# button_board_v0_3_1.net
KiCad netlist of a schematic drawn in EAGLE
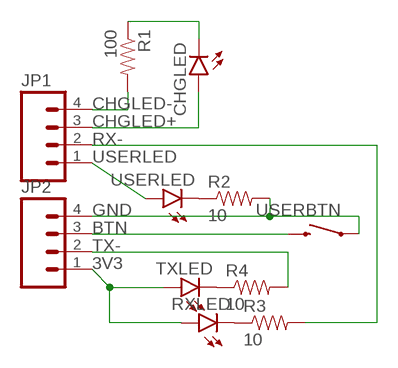
[diagram p0: schematic, sheet 1]

(export (version "E")
  (design (tool "Eeschema 10.0.6"))
  (components
    (comp (ref "CHGLED")
      (value "LED-FKIT-1206")
      (footprint "eagle-import:FKIT-LED-1206")
      (libsource (lib "eagle-import") (part "LED-FKIT-1206"))
    )
    (comp (ref "JP1")
      (value "M04PTH")
      (footprint "eagle-import:1X04")
      (libsource (lib "eagle-import") (part "M04PTH"))
    )
    (comp (ref "JP2")
      (value "M04PTH")
      (footprint "eagle-import:1X04")
      (libsource (lib "eagle-import") (part "M04PTH"))
    )
    (comp (ref "R1")
      (value "100")
      (footprint "eagle-import:0603-RES")
      (libsource (lib "eagle-import") (part "RESISTOR0603-RES"))
    )
    (comp (ref "R2")
      (value "10")
      (footprint "eagle-import:0603-RES")
      (libsource (lib "eagle-import") (part "RESISTOR0603-RES"))
    )
    (comp (ref "R3")
      (value "10")
      (footprint "eagle-import:0603-RES")
      (libsource (lib "eagle-import") (part "RESISTOR0603-RES"))
    )
    (comp (ref "R4")
      (value "10")
      (footprint "eagle-import:0603-RES")
      (libsource (lib "eagle-import") (part "RESISTOR0603-RES"))
    )
    (comp (ref "RXLED")
      (value "LED-FKIT-1206")
      (footprint "eagle-import:FKIT-LED-1206")
      (libsource (lib "eagle-import") (part "LED-FKIT-1206"))
    )
    (comp (ref "TXLED")
      (value "LED-FKIT-1206")
      (footprint "eagle-import:FKIT-LED-1206")
      (libsource (lib "eagle-import") (part "LED-FKIT-1206"))
    )
    (comp (ref "USERBTN")
      (value "SWITCH-MOMENTARY-2PCB_MOUNTSMD_OMRON_B3S_100X")
      (footprint "eagle-import:TACTILE_SWITCH_LARGE")
      (libsource (lib "eagle-import") (part "SWITCH-MOMENTARY-2SMD_OMRON_B3S_100XPCB_MOUNT"))
    )
    (comp (ref "USERLED")
      (value "LED-FKIT-1206")
      (footprint "eagle-import:FKIT-LED-1206")
      (libsource (lib "eagle-import") (part "LED-FKIT-1206"))
    )
  )
  (nets
    (net (code "1") (name "/3V3") (class "Default")
      (node (ref "JP2") (pin "1") (pinfunction "1_1") (pintype "passive"))
      (node (ref "RXLED") (pin "A") (pinfunction "A_A") (pintype "passive"))
      (node (ref "TXLED") (pin "A") (pinfunction "A_A") (pintype "passive"))
    )
    (net (code "2") (name "/BTN") (class "Default")
      (node (ref "JP2") (pin "3") (pinfunction "3_3") (pintype "passive"))
      (node (ref "USERBTN") (pin "3") (pinfunction "2_3") (pintype "passive"))
    )
    (net (code "3") (name "/CHGLED+") (class "Default")
      (node (ref "CHGLED") (pin "A") (pinfunction "A_A") (pintype "passive"))
      (node (ref "JP1") (pin "3") (pinfunction "3_3") (pintype "passive"))
    )
    (net (code "4") (name "/CHGLED-") (class "Default")
      (node (ref "JP1") (pin "4") (pinfunction "4_4") (pintype "passive"))
      (node (ref "R1") (pin "2") (pinfunction "2_2") (pintype "passive"))
    )
    (net (code "5") (name "/GND") (class "Default")
      (node (ref "JP2") (pin "4") (pinfunction "4_4") (pintype "passive"))
      (node (ref "R2") (pin "2") (pinfunction "2_2") (pintype "passive"))
      (node (ref "USERBTN") (pin "1") (pinfunction "1_1") (pintype "passive"))
    )
    (net (code "6") (name "/RX-") (class "Default")
      (node (ref "JP1") (pin "2") (pinfunction "2_2") (pintype "passive"))
      (node (ref "R3") (pin "2") (pinfunction "2_2") (pintype "passive"))
    )
    (net (code "7") (name "/TX-") (class "Default")
      (node (ref "JP2") (pin "2") (pinfunction "2_2") (pintype "passive"))
      (node (ref "R4") (pin "2") (pinfunction "2_2") (pintype "passive"))
    )
    (net (code "8") (name "/USERLED") (class "Default")
      (node (ref "JP1") (pin "1") (pinfunction "1_1") (pintype "passive"))
      (node (ref "USERLED") (pin "A") (pinfunction "A_A") (pintype "passive"))
    )
    (net (code "9") (name "Net-(CHGLED-PadC)") (class "Default")
      (node (ref "CHGLED") (pin "C") (pinfunction "C_C") (pintype "passive"))
      (node (ref "R1") (pin "1") (pinfunction "1_1") (pintype "passive"))
    )
    (net (code "10") (name "Net-(R2-Pad1)") (class "Default")
      (node (ref "R2") (pin "1") (pinfunction "1_1") (pintype "passive"))
      (node (ref "USERLED") (pin "C") (pinfunction "C_C") (pintype "passive"))
    )
    (net (code "11") (name "Net-(R3-Pad1)") (class "Default")
      (node (ref "R3") (pin "1") (pinfunction "1_1") (pintype "passive"))
      (node (ref "RXLED") (pin "C") (pinfunction "C_C") (pintype "passive"))
    )
    (net (code "12") (name "Net-(R4-Pad1)") (class "Default")
      (node (ref "R4") (pin "1") (pinfunction "1_1") (pintype "passive"))
      (node (ref "TXLED") (pin "C") (pinfunction "C_C") (pintype "passive"))
    )
  )
)
